# ip_phone_f_power.net
KiCad netlist of a schematic drawn in Altium Designer
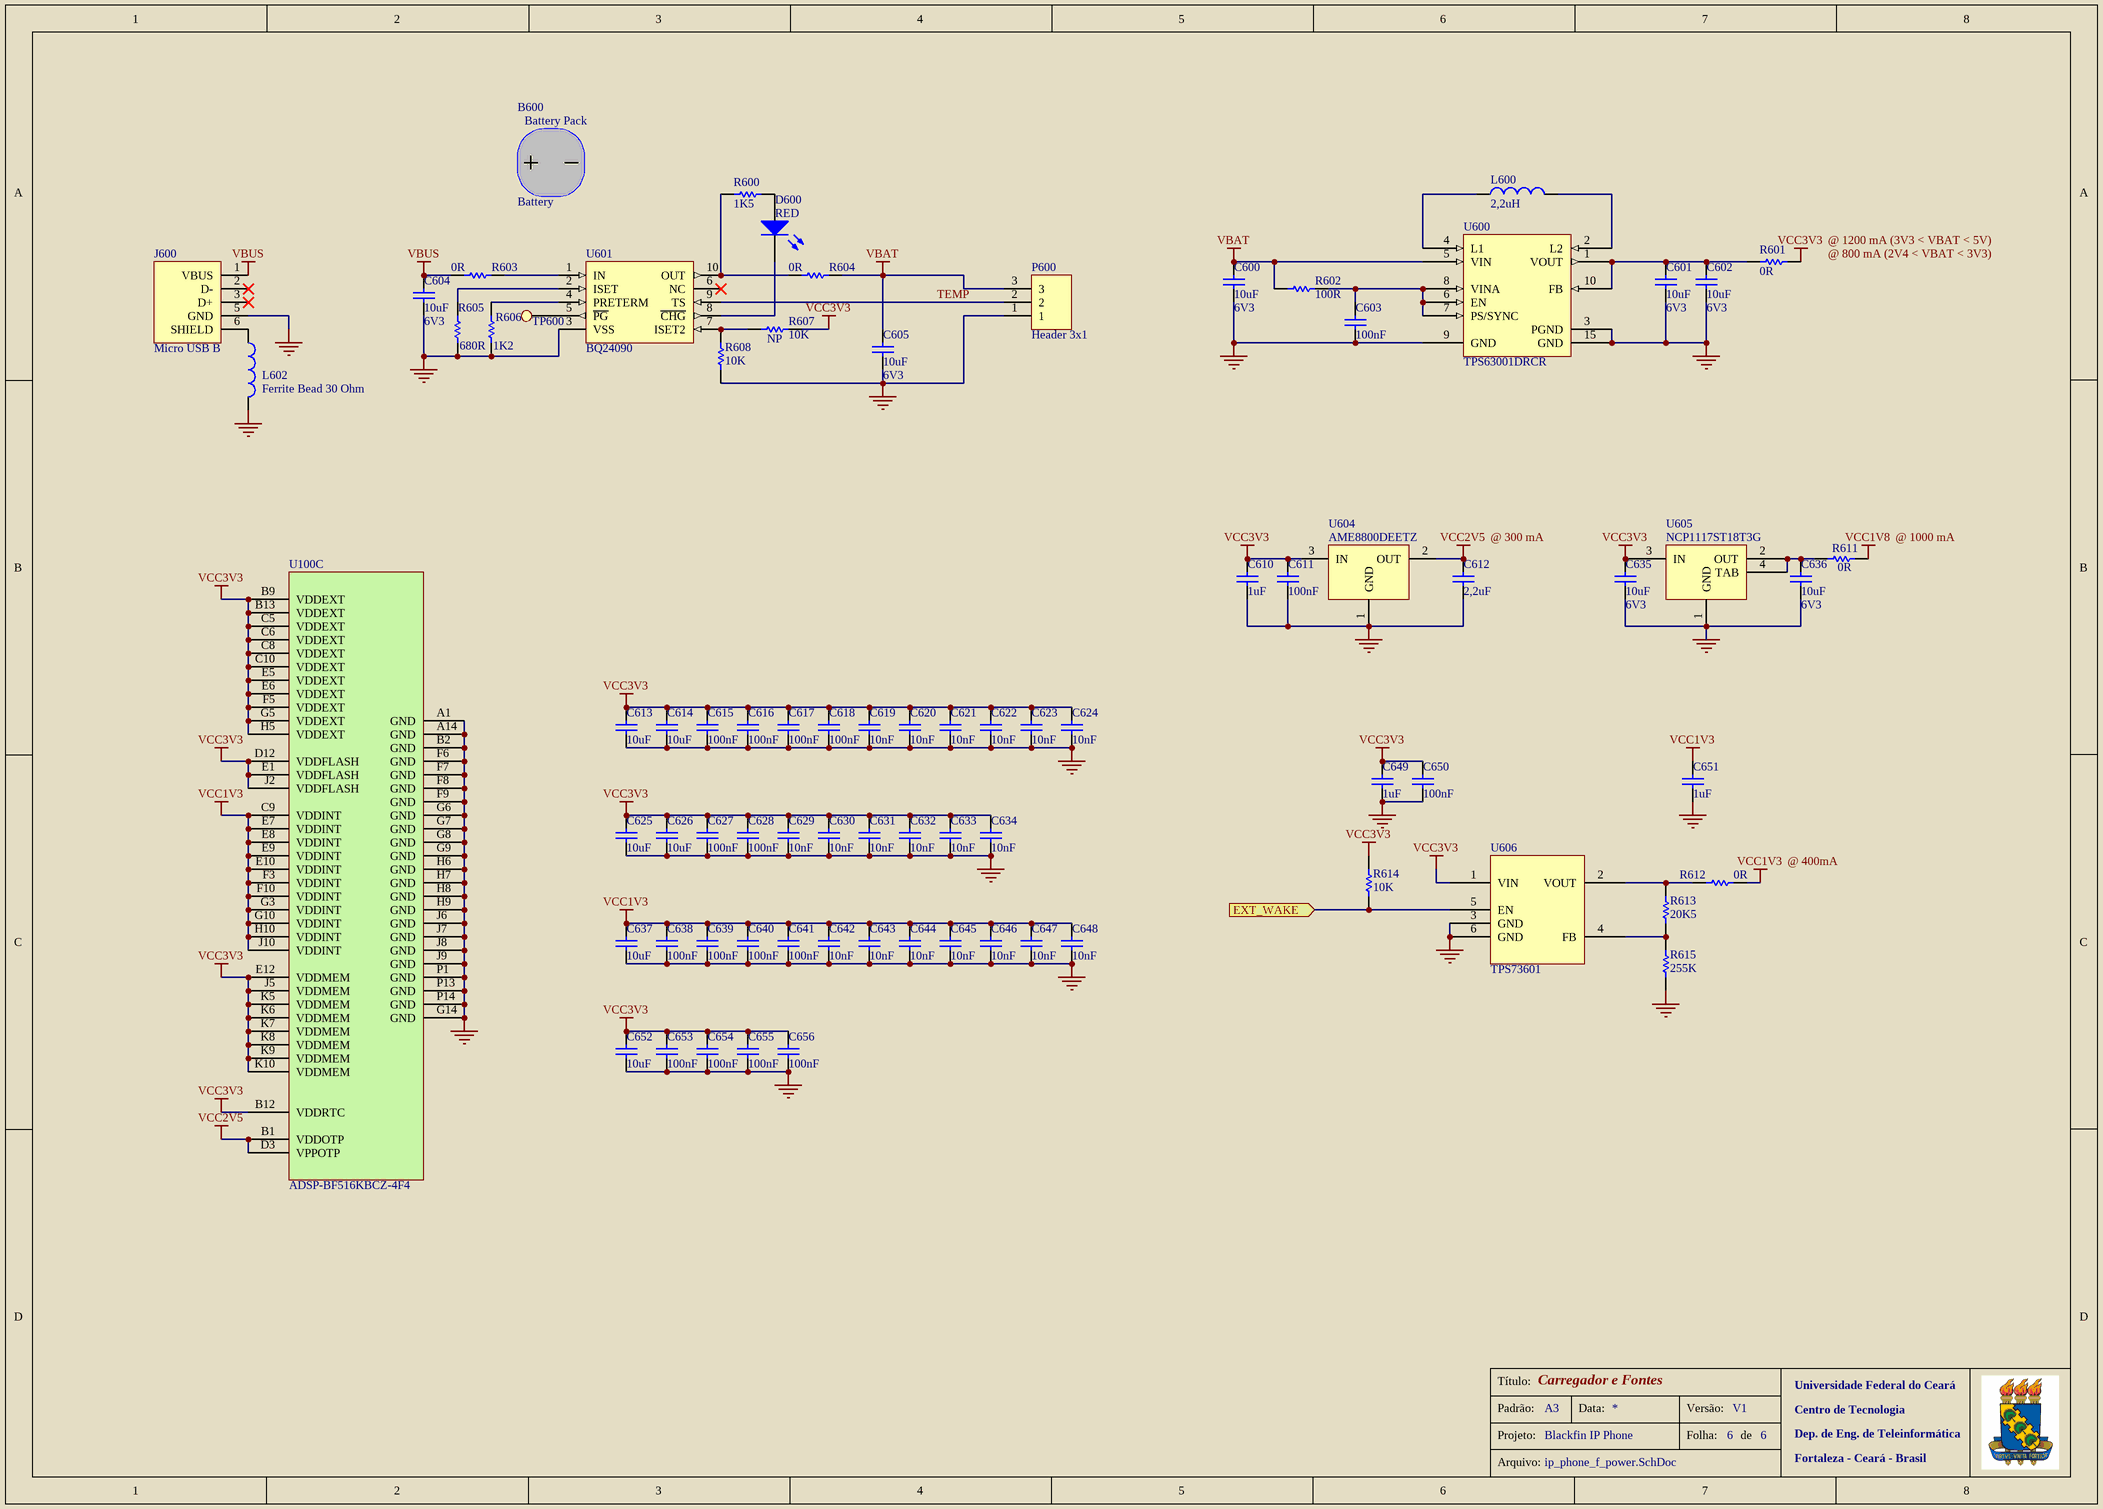
[diagram p0: ip_phone_f_power.SchDoc]

(export (version "E")
  (design (tool "Eeschema 10.0.6"))
  (components
    (comp (ref "B600")
      (value "Battery")
      (description "Li-Polymer battery PL714065, 3.7V 2000mAh cell")
      (fields (field (name "EVENDORPART#") "PC-714065") (field (name "MANUFACTURER") "HOLY TECHNOLOGY"))
      (libsource (lib "ip_phone") (part "Battery"))
    )
    (comp (ref "C600")
      (value "10uF")
      (footprint "ip_phone:CC1608-0603")
      (description "Capacitor SMD/SMT 0603 10uF 6.3volts X5R 20%")
      (fields (field (name "EVENDORPART#") "810-C2012Y5V1A106Z") (field (name "MANUFACTURER") "TDK"))
      (libsource (lib "ip_phone") (part "Capacitor"))
    )
    (comp (ref "C601")
      (value "10uF")
      (footprint "ip_phone:CC1608-0603")
      (description "Capacitor SMD/SMT 0603 10uF 6.3volts X5R 20%")
      (fields (field (name "EVENDORPART#") "810-C2012Y5V1A106Z") (field (name "MANUFACTURER") "TDK"))
      (libsource (lib "ip_phone") (part "Capacitor"))
    )
    (comp (ref "C602")
      (value "10uF")
      (footprint "ip_phone:CC1608-0603")
      (description "Capacitor SMD/SMT 0603 10uF 6.3volts X5R 20%")
      (fields (field (name "EVENDORPART#") "810-C2012Y5V1A106Z") (field (name "MANUFACTURER") "TDK"))
      (libsource (lib "ip_phone") (part "Capacitor"))
    )
    (comp (ref "C603")
      (value "100nF")
      (footprint "ip_phone:CC1005-0402")
      (description "MLCC - SMD/SMT 0.1UF 16V 10% 0402")
      (fields (field (name "EVENDORPART#") "810-C1005X7R1C104K") (field (name "MANUFACTURER") "TDK"))
      (libsource (lib "ip_phone") (part "Capacitor"))
    )
    (comp (ref "C604")
      (value "10uF")
      (footprint "ip_phone:CC1608-0603")
      (description "Capacitor SMD/SMT 0603 10uF 6.3volts X5R 20%")
      (fields (field (name "EVENDORPART#") "810-C2012Y5V1A106Z") (field (name "MANUFACTURER") "TDK"))
      (libsource (lib "ip_phone") (part "Capacitor"))
    )
    (comp (ref "C605")
      (value "10uF")
      (footprint "ip_phone:CC1608-0603")
      (description "Capacitor SMD/SMT 0603 10uF 6.3volts X5R 20%")
      (fields (field (name "EVENDORPART#") "810-C2012Y5V1A106Z") (field (name "MANUFACTURER") "TDK"))
      (libsource (lib "ip_phone") (part "Capacitor"))
    )
    (comp (ref "C610")
      (value "1uF")
      (footprint "ip_phone:CC1005-0402")
      (description "CAP CER 1.0UF 6.3V 20% X5R 0402")
      (fields
        (field (name "EVENDORPART#") "490-1319-1-ND")
        (field (name "MANUFACTURER") "Murata Electronics North America")
      )
      (libsource (lib "ip_phone") (part "Capacitor"))
    )
    (comp (ref "C611")
      (value "100nF")
      (footprint "ip_phone:CC1005-0402")
      (description "MLCC - SMD/SMT 0.1UF 16V 10% 0402")
      (fields (field (name "EVENDORPART#") "810-C1005X7R1C104K") (field (name "MANUFACTURER") "TDK"))
      (libsource (lib "ip_phone") (part "Capacitor"))
    )
    (comp (ref "C612")
      (value "2,2uF")
      (footprint "ip_phone:CC1608-0603")
      (description "Capacitor SMD/SMT 0603 2.2uF 10volts Y5V +80-20%")
      (fields (field (name "EVENDORPART#") "81-GRM188F51A225ZE01") (field (name "MANUFACTURER") "Murata"))
      (libsource (lib "ip_phone") (part "Capacitor"))
    )
    (comp (ref "C613")
      (value "10uF")
      (footprint "ip_phone:CC1608-0603")
      (description "Capacitor SMD/SMT 0603 10uF 6.3volts X5R 20%")
      (fields (field (name "EVENDORPART#") "810-C2012Y5V1A106Z") (field (name "MANUFACTURER") "TDK"))
      (libsource (lib "ip_phone") (part "Capacitor"))
    )
    (comp (ref "C614")
      (value "10uF")
      (footprint "ip_phone:CC1608-0603")
      (description "Capacitor SMD/SMT 0603 10uF 6.3volts X5R 20%")
      (fields (field (name "EVENDORPART#") "810-C2012Y5V1A106Z") (field (name "MANUFACTURER") "TDK"))
      (libsource (lib "ip_phone") (part "Capacitor"))
    )
    (comp (ref "C615")
      (value "100nF")
      (footprint "ip_phone:CC1005-0402")
      (description "MLCC - SMD/SMT 0.1UF 16V 10% 0402")
      (fields (field (name "EVENDORPART#") "810-C1005X7R1C104K") (field (name "MANUFACTURER") "TDK"))
      (libsource (lib "ip_phone") (part "Capacitor"))
    )
    (comp (ref "C616")
      (value "100nF")
      (footprint "ip_phone:CC1005-0402")
      (description "MLCC - SMD/SMT 0.1UF 16V 10% 0402")
      (fields (field (name "EVENDORPART#") "810-C1005X7R1C104K") (field (name "MANUFACTURER") "TDK"))
      (libsource (lib "ip_phone") (part "Capacitor"))
    )
    (comp (ref "C617")
      (value "100nF")
      (footprint "ip_phone:CC1005-0402")
      (description "MLCC - SMD/SMT 0.1UF 16V 10% 0402")
      (fields (field (name "EVENDORPART#") "810-C1005X7R1C104K") (field (name "MANUFACTURER") "TDK"))
      (libsource (lib "ip_phone") (part "Capacitor"))
    )
    (comp (ref "C618")
      (value "100nF")
      (footprint "ip_phone:CC1005-0402")
      (description "MLCC - SMD/SMT 0.1UF 16V 10% 0402")
      (fields (field (name "EVENDORPART#") "810-C1005X7R1C104K") (field (name "MANUFACTURER") "TDK"))
      (libsource (lib "ip_phone") (part "Capacitor"))
    )
    (comp (ref "C619")
      (value "10nF")
      (footprint "ip_phone:CC1005-0402")
      (description "Capacitor SMD/SMT 0402 0.01uF 16volts X7R 10%")
      (fields (field (name "EVENDORPART#") "810-C1005X7R1C103K") (field (name "MANUFACTURER") "TDK"))
      (libsource (lib "ip_phone") (part "Capacitor"))
    )
    (comp (ref "C620")
      (value "10nF")
      (footprint "ip_phone:CC1005-0402")
      (description "Capacitor SMD/SMT 0402 0.01uF 16volts X7R 10%")
      (fields (field (name "EVENDORPART#") "810-C1005X7R1C103K") (field (name "MANUFACTURER") "TDK"))
      (libsource (lib "ip_phone") (part "Capacitor"))
    )
    (comp (ref "C621")
      (value "10nF")
      (footprint "ip_phone:CC1005-0402")
      (description "Capacitor SMD/SMT 0402 0.01uF 16volts X7R 10%")
      (fields (field (name "EVENDORPART#") "810-C1005X7R1C103K") (field (name "MANUFACTURER") "TDK"))
      (libsource (lib "ip_phone") (part "Capacitor"))
    )
    (comp (ref "C622")
      (value "10nF")
      (footprint "ip_phone:CC1005-0402")
      (description "Capacitor SMD/SMT 0402 0.01uF 16volts X7R 10%")
      (fields (field (name "EVENDORPART#") "810-C1005X7R1C103K") (field (name "MANUFACTURER") "TDK"))
      (libsource (lib "ip_phone") (part "Capacitor"))
    )
    (comp (ref "C623")
      (value "10nF")
      (footprint "ip_phone:CC1005-0402")
      (description "Capacitor SMD/SMT 0402 0.01uF 16volts X7R 10%")
      (fields (field (name "EVENDORPART#") "810-C1005X7R1C103K") (field (name "MANUFACTURER") "TDK"))
      (libsource (lib "ip_phone") (part "Capacitor"))
    )
    (comp (ref "C624")
      (value "10nF")
      (footprint "ip_phone:CC1005-0402")
      (description "Capacitor SMD/SMT 0402 0.01uF 16volts X7R 10%")
      (fields (field (name "EVENDORPART#") "810-C1005X7R1C103K") (field (name "MANUFACTURER") "TDK"))
      (libsource (lib "ip_phone") (part "Capacitor"))
    )
    (comp (ref "C625")
      (value "10uF")
      (footprint "ip_phone:CC1608-0603")
      (description "Capacitor SMD/SMT 0603 10uF 6.3volts X5R 20%")
      (fields (field (name "EVENDORPART#") "810-C2012Y5V1A106Z") (field (name "MANUFACTURER") "TDK"))
      (libsource (lib "ip_phone") (part "Capacitor"))
    )
    (comp (ref "C626")
      (value "10uF")
      (footprint "ip_phone:CC1608-0603")
      (description "Capacitor SMD/SMT 0603 10uF 6.3volts X5R 20%")
      (fields (field (name "EVENDORPART#") "810-C2012Y5V1A106Z") (field (name "MANUFACTURER") "TDK"))
      (libsource (lib "ip_phone") (part "Capacitor"))
    )
    (comp (ref "C627")
      (value "100nF")
      (footprint "ip_phone:CC1005-0402")
      (description "MLCC - SMD/SMT 0.1UF 16V 10% 0402")
      (fields (field (name "EVENDORPART#") "810-C1005X7R1C104K") (field (name "MANUFACTURER") "TDK"))
      (libsource (lib "ip_phone") (part "Capacitor"))
    )
    (comp (ref "C628")
      (value "100nF")
      (footprint "ip_phone:CC1005-0402")
      (description "MLCC - SMD/SMT 0.1UF 16V 10% 0402")
      (fields (field (name "EVENDORPART#") "810-C1005X7R1C104K") (field (name "MANUFACTURER") "TDK"))
      (libsource (lib "ip_phone") (part "Capacitor"))
    )
    (comp (ref "C629")
      (value "10nF")
      (footprint "ip_phone:CC1005-0402")
      (description "Capacitor SMD/SMT 0402 0.01uF 16volts X7R 10%")
      (fields (field (name "EVENDORPART#") "810-C1005X7R1C103K") (field (name "MANUFACTURER") "TDK"))
      (libsource (lib "ip_phone") (part "Capacitor"))
    )
    (comp (ref "C630")
      (value "10nF")
      (footprint "ip_phone:CC1005-0402")
      (description "Capacitor SMD/SMT 0402 0.01uF 16volts X7R 10%")
      (fields (field (name "EVENDORPART#") "810-C1005X7R1C103K") (field (name "MANUFACTURER") "TDK"))
      (libsource (lib "ip_phone") (part "Capacitor"))
    )
    (comp (ref "C631")
      (value "10nF")
      (footprint "ip_phone:CC1005-0402")
      (description "Capacitor SMD/SMT 0402 0.01uF 16volts X7R 10%")
      (fields (field (name "EVENDORPART#") "810-C1005X7R1C103K") (field (name "MANUFACTURER") "TDK"))
      (libsource (lib "ip_phone") (part "Capacitor"))
    )
    (comp (ref "C632")
      (value "10nF")
      (footprint "ip_phone:CC1005-0402")
      (description "Capacitor SMD/SMT 0402 0.01uF 16volts X7R 10%")
      (fields (field (name "EVENDORPART#") "810-C1005X7R1C103K") (field (name "MANUFACTURER") "TDK"))
      (libsource (lib "ip_phone") (part "Capacitor"))
    )
    (comp (ref "C633")
      (value "10nF")
      (footprint "ip_phone:CC1005-0402")
      (description "Capacitor SMD/SMT 0402 0.01uF 16volts X7R 10%")
      (fields (field (name "EVENDORPART#") "810-C1005X7R1C103K") (field (name "MANUFACTURER") "TDK"))
      (libsource (lib "ip_phone") (part "Capacitor"))
    )
    (comp (ref "C634")
      (value "10nF")
      (footprint "ip_phone:CC1005-0402")
      (description "Capacitor SMD/SMT 0402 0.01uF 16volts X7R 10%")
      (fields (field (name "EVENDORPART#") "810-C1005X7R1C103K") (field (name "MANUFACTURER") "TDK"))
      (libsource (lib "ip_phone") (part "Capacitor"))
    )
    (comp (ref "C635")
      (value "10uF")
      (footprint "ip_phone:CC1608-0603")
      (description "Capacitor SMD/SMT 0603 10uF 6.3volts X5R 20%")
      (fields (field (name "EVENDORPART#") "810-C2012Y5V1A106Z") (field (name "MANUFACTURER") "TDK"))
      (libsource (lib "ip_phone") (part "Capacitor"))
    )
    (comp (ref "C636")
      (value "10uF")
      (footprint "ip_phone:CC1608-0603")
      (description "Capacitor SMD/SMT 0603 10uF 6.3volts X5R 20%")
      (fields (field (name "EVENDORPART#") "810-C2012Y5V1A106Z") (field (name "MANUFACTURER") "TDK"))
      (libsource (lib "ip_phone") (part "Capacitor"))
    )
    (comp (ref "C637")
      (value "10uF")
      (footprint "ip_phone:CC1608-0603")
      (description "Capacitor SMD/SMT 0603 10uF 6.3volts X5R 20%")
      (fields (field (name "EVENDORPART#") "810-C2012Y5V1A106Z") (field (name "MANUFACTURER") "TDK"))
      (libsource (lib "ip_phone") (part "Capacitor"))
    )
    (comp (ref "C638")
      (value "100nF")
      (footprint "ip_phone:CC1005-0402")
      (description "MLCC - SMD/SMT 0.1UF 16V 10% 0402")
      (fields (field (name "EVENDORPART#") "810-C1005X7R1C104K") (field (name "MANUFACTURER") "TDK"))
      (libsource (lib "ip_phone") (part "Capacitor"))
    )
    (comp (ref "C639")
      (value "100nF")
      (footprint "ip_phone:CC1005-0402")
      (description "MLCC - SMD/SMT 0.1UF 16V 10% 0402")
      (fields (field (name "EVENDORPART#") "810-C1005X7R1C104K") (field (name "MANUFACTURER") "TDK"))
      (libsource (lib "ip_phone") (part "Capacitor"))
    )
    (comp (ref "C640")
      (value "100nF")
      (footprint "ip_phone:CC1005-0402")
      (description "MLCC - SMD/SMT 0.1UF 16V 10% 0402")
      (fields (field (name "EVENDORPART#") "810-C1005X7R1C104K") (field (name "MANUFACTURER") "TDK"))
      (libsource (lib "ip_phone") (part "Capacitor"))
    )
    (comp (ref "C641")
      (value "100nF")
      (footprint "ip_phone:CC1005-0402")
      (description "MLCC - SMD/SMT 0.1UF 16V 10% 0402")
      (fields (field (name "EVENDORPART#") "810-C1005X7R1C104K") (field (name "MANUFACTURER") "TDK"))
      (libsource (lib "ip_phone") (part "Capacitor"))
    )
    (comp (ref "C642")
      (value "10nF")
      (footprint "ip_phone:CC1005-0402")
      (description "Capacitor SMD/SMT 0402 0.01uF 16volts X7R 10%")
      (fields (field (name "EVENDORPART#") "810-C1005X7R1C103K") (field (name "MANUFACTURER") "TDK"))
      (libsource (lib "ip_phone") (part "Capacitor"))
    )
    (comp (ref "C643")
      (value "10nF")
      (footprint "ip_phone:CC1005-0402")
      (description "Capacitor SMD/SMT 0402 0.01uF 16volts X7R 10%")
      (fields (field (name "EVENDORPART#") "810-C1005X7R1C103K") (field (name "MANUFACTURER") "TDK"))
      (libsource (lib "ip_phone") (part "Capacitor"))
    )
    (comp (ref "C644")
      (value "10nF")
      (footprint "ip_phone:CC1005-0402")
      (description "Capacitor SMD/SMT 0402 0.01uF 16volts X7R 10%")
      (fields (field (name "EVENDORPART#") "810-C1005X7R1C103K") (field (name "MANUFACTURER") "TDK"))
      (libsource (lib "ip_phone") (part "Capacitor"))
    )
    (comp (ref "C645")
      (value "10nF")
      (footprint "ip_phone:CC1005-0402")
      (description "Capacitor SMD/SMT 0402 0.01uF 16volts X7R 10%")
      (fields (field (name "EVENDORPART#") "810-C1005X7R1C103K") (field (name "MANUFACTURER") "TDK"))
      (libsource (lib "ip_phone") (part "Capacitor"))
    )
    (comp (ref "C646")
      (value "10nF")
      (footprint "ip_phone:CC1005-0402")
      (description "Capacitor SMD/SMT 0402 0.01uF 16volts X7R 10%")
      (fields (field (name "EVENDORPART#") "810-C1005X7R1C103K") (field (name "MANUFACTURER") "TDK"))
      (libsource (lib "ip_phone") (part "Capacitor"))
    )
    (comp (ref "C647")
      (value "10nF")
      (footprint "ip_phone:CC1005-0402")
      (description "Capacitor SMD/SMT 0402 0.01uF 16volts X7R 10%")
      (fields (field (name "EVENDORPART#") "810-C1005X7R1C103K") (field (name "MANUFACTURER") "TDK"))
      (libsource (lib "ip_phone") (part "Capacitor"))
    )
    (comp (ref "C648")
      (value "10nF")
      (footprint "ip_phone:CC1005-0402")
      (description "Capacitor SMD/SMT 0402 0.01uF 16volts X7R 10%")
      (fields (field (name "EVENDORPART#") "810-C1005X7R1C103K") (field (name "MANUFACTURER") "TDK"))
      (libsource (lib "ip_phone") (part "Capacitor"))
    )
    (comp (ref "C649")
      (value "1uF")
      (footprint "ip_phone:CC1005-0402")
      (description "CAP CER 1.0UF 6.3V 20% X5R 0402")
      (fields
        (field (name "EVENDORPART#") "490-1319-1-ND")
        (field (name "MANUFACTURER") "Murata Electronics North America")
      )
      (libsource (lib "ip_phone") (part "Capacitor"))
    )
    (comp (ref "C650")
      (value "100nF")
      (footprint "ip_phone:CC1005-0402")
      (description "MLCC - SMD/SMT 0.1UF 16V 10% 0402")
      (fields (field (name "EVENDORPART#") "810-C1005X7R1C104K") (field (name "MANUFACTURER") "TDK"))
      (libsource (lib "ip_phone") (part "Capacitor"))
    )
    (comp (ref "C651")
      (value "1uF")
      (footprint "ip_phone:CC1005-0402")
      (description "CAP CER 1.0UF 6.3V 20% X5R 0402")
      (fields
        (field (name "EVENDORPART#") "490-1319-1-ND")
        (field (name "MANUFACTURER") "Murata Electronics North America")
      )
      (libsource (lib "ip_phone") (part "Capacitor"))
    )
    (comp (ref "C652")
      (value "10uF")
      (footprint "ip_phone:CC1608-0603")
      (description "Capacitor SMD/SMT 0603 10uF 6.3volts X5R 20%")
      (fields (field (name "EVENDORPART#") "810-C2012Y5V1A106Z") (field (name "MANUFACTURER") "TDK"))
      (libsource (lib "ip_phone") (part "Capacitor"))
    )
    (comp (ref "C653")
      (value "100nF")
      (footprint "ip_phone:CC1005-0402")
      (description "MLCC - SMD/SMT 0.1UF 16V 10% 0402")
      (fields (field (name "EVENDORPART#") "810-C1005X7R1C104K") (field (name "MANUFACTURER") "TDK"))
      (libsource (lib "ip_phone") (part "Capacitor"))
    )
    (comp (ref "C654")
      (value "100nF")
      (footprint "ip_phone:CC1005-0402")
      (description "MLCC - SMD/SMT 0.1UF 16V 10% 0402")
      (fields (field (name "EVENDORPART#") "810-C1005X7R1C104K") (field (name "MANUFACTURER") "TDK"))
      (libsource (lib "ip_phone") (part "Capacitor"))
    )
    (comp (ref "C655")
      (value "100nF")
      (footprint "ip_phone:CC1005-0402")
      (description "MLCC - SMD/SMT 0.1UF 16V 10% 0402")
      (fields (field (name "EVENDORPART#") "810-C1005X7R1C104K") (field (name "MANUFACTURER") "TDK"))
      (libsource (lib "ip_phone") (part "Capacitor"))
    )
    (comp (ref "C656")
      (value "100nF")
      (footprint "ip_phone:CC1005-0402")
      (description "MLCC - SMD/SMT 0.1UF 16V 10% 0402")
      (fields (field (name "EVENDORPART#") "810-C1005X7R1C104K") (field (name "MANUFACTURER") "TDK"))
      (libsource (lib "ip_phone") (part "Capacitor"))
    )
    (comp (ref "D600")
      (value "RED")
      (footprint "ip_phone:LED_0603")
      (description "LED")
      (fields (field (name "PART#") "APT1608SURCK") (field (name "MANUFACTURER") "Kingbright"))
      (libsource (lib "ip_phone") (part "LED"))
    )
    (comp (ref "J600")
      (value "Micro USB B")
      (footprint "ip_phone:Micro USB")
      (description "USB Connectors 5P Quick Connect Micro USB TypeB Rcpt")
      (fields (field (name "MANUFACTURER") "FCI") (field (name "PART#") "10103594-0001LF"))
      (libsource (lib "ip_phone") (part "CON_Micro_USB"))
    )
    (comp (ref "L600")
      (value "2,2uH")
      (footprint "ip_phone:POWER INDUCTOR")
      (description "IND POWER 2.2UH 1.5A SMD")
      (fields (field (name "EVENDORPART#") "445-3233-1-ND") (field (name "MANUFACTURER") "TDK"))
      (libsource (lib "ip_phone") (part "Inductor"))
    )
    (comp (ref "L602")
      (value "Ferrite Bead 30 Ohm")
      (footprint "ip_phone:INDUTOR_0603")
      (description "EMI/RFI Suppressors & Ferrites 0603 30 OHM")
      (fields (field (name "EVENDORPART#") "81-BLM11P300S") (field (name "MANUFACTURER") "Murata"))
      (libsource (lib "ip_phone") (part "Inductor"))
    )
    (comp (ref "P600")
      (value "Header 3x1")
      (footprint "ip_phone:HEADER 3x1")
      (description "CONN HEADER 3POS 2.5MM R/A SMD")
      (fields
        (field (name "MANUFACTURER") "JST Sales America Inc")
        (field (name "PART#") "S3B-XH-SM4-TB(LF)(SN)")
      )
      (libsource (lib "ip_phone") (part "CON_HEADER_3x1"))
    )
    (comp (ref "R600")
      (value "1K5")
      (footprint "ip_phone:CR1608-0603")
      (description "Thick Film Resistors 1.5KOHM 5% 1/10W")
      (fields (field (name "EVENDORPART#") "52-CR0603-JW-152GLF") (field (name "MANUFACTURER") "Bourns"))
      (libsource (lib "ip_phone") (part "Resistor"))
    )
    (comp (ref "R601")
      (value "0R")
      (footprint "ip_phone:CR3225-1210")
      (description "Thick Film Resistors ZERO OHM JUMPER 1210")
      (fields (field (name "EVENDORPART#") "660-RK73Z2ETTD") (field (name "MANUFACTURER") "KOA Speer"))
      (libsource (lib "ip_phone") (part "Resistor"))
    )
    (comp (ref "R602")
      (value "100R")
      (footprint "ip_phone:CR1608-0603")
      (description "Thick Film Resistors 1/16WATT 100R 0402")
      (fields (field (name "EVENDORPART#") "652-CR0603-JW-101GLF") (field (name "MANUFACTURER") "Bourns"))
      (libsource (lib "ip_phone") (part "Resistor"))
    )
    (comp (ref "R603")
      (value "0R")
      (footprint "ip_phone:CR1608-0603")
      (description "Thick Film Resistors ZERO OHM")
      (fields (field (name "EVENDORPART#") "652-CR0603-J/-000ELF") (field (name "MANUFACTURER") "Bourns"))
      (libsource (lib "ip_phone") (part "Resistor"))
    )
    (comp (ref "R604")
      (value "0R")
      (footprint "ip_phone:CR1608-0603")
      (description "Thick Film Resistors ZERO OHM")
      (fields (field (name "EVENDORPART#") "652-CR0603-J/-000ELF") (field (name "MANUFACTURER") "Bourns"))
      (libsource (lib "ip_phone") (part "Resistor"))
    )
    (comp (ref "R605")
      (value "680R")
      (footprint "ip_phone:CR1005-0402")
      (description "Thick Film Resistors SMD 0402 680 5%  1/16 W")
      (fields (field (name "EVENDORPART#") "311-680JRCT-ND") (field (name "MANUFACTURER") "Yageo"))
      (libsource (lib "ip_phone") (part "Resistor"))
    )
    (comp (ref "R606")
      (value "1K2")
      (footprint "ip_phone:CR1005-0402")
      (description "Thick Film Resistors SMD 0402 1K2 5%  1/16 W")
      (fields (field (name "EVENDORPART#") "311-1.2KJRCT-ND") (field (name "MANUFACTURER") "Yageo"))
      (libsource (lib "ip_phone") (part "Resistor"))
    )
    (comp (ref "R607")
      (value "10K")
      (footprint "ip_phone:CR1005-0402")
      (description "Thick Film Resistors SMD 0402 10k 5%  1/16 W")
      (fields
        (field (name "EVENDORPART#") "311-10KJRCT-ND")
        (field (name "MANUFACTURER") "Yageo")
        (field (name "NP") "NP")
      )
      (libsource (lib "ip_phone") (part "Resistor"))
    )
    (comp (ref "R608")
      (value "10K")
      (footprint "ip_phone:CR1005-0402")
      (description "Thick Film Resistors SMD 0402 10k 5%  1/16 W")
      (fields (field (name "EVENDORPART#") "311-10KJRCT-ND") (field (name "MANUFACTURER") "Yageo"))
      (libsource (lib "ip_phone") (part "Resistor"))
    )
    (comp (ref "R611")
      (value "0R")
      (footprint "ip_phone:CR3225-1210")
      (description "Thick Film Resistors ZERO OHM JUMPER 1210")
      (fields (field (name "EVENDORPART#") "660-RK73Z2ETTD") (field (name "MANUFACTURER") "KOA Speer"))
      (libsource (lib "ip_phone") (part "Resistor"))
    )
    (comp (ref "R612")
      (value "0R")
      (footprint "ip_phone:CR1608-0603")
      (description "Thick Film Resistors ZERO OHM")
      (fields (field (name "EVENDORPART#") "652-CR0603-J/-000ELF") (field (name "MANUFACTURER") "Bourns"))
      (libsource (lib "ip_phone") (part "Resistor"))
    )
    (comp (ref "R613")
      (value "20K5")
      (footprint "ip_phone:CR1005-0402")
      (description "RES 20.5K OHM 1/10W 1% 0402 SMD")
      (fields (field (name "EVENDORPART#") "P20.5KLCT-ND") (field (name "MANUFACTURER") "Panasonic - ECG"))
      (libsource (lib "ip_phone") (part "Resistor"))
    )
    (comp (ref "R614")
      (value "10K")
      (footprint "ip_phone:CR1005-0402")
      (description "Thick Film Resistors SMD 0402 10k 5%  1/16 W")
      (fields (field (name "EVENDORPART#") "311-10KJRCT-ND") (field (name "MANUFACTURER") "Yageo"))
      (libsource (lib "ip_phone") (part "Resistor"))
    )
    (comp (ref "R615")
      (value "255K")
      (footprint "ip_phone:CR1005-0402")
      (description "RES 255K OHM 1/10W 1% 0402 SMD")
      (fields (field (name "EVENDORPART#") "P255KLCT-ND") (field (name "MANUFACTURER") "Panasonic - ECG"))
      (libsource (lib "ip_phone") (part "Resistor"))
    )
    (comp (ref "TP600")
      (value "Test Point")
      (footprint "ip_phone:Test Point")
      (fields (field (name "EVENDORPART#") "NÃO SE APLICA"))
      (libsource (lib "ip_phone") (part "Test Point"))
    )
    (comp (ref "U100")
      (value "ADSP-BF516KBCZ-4F4")
      (footprint "ip_phone:BGA168")
      (description "Low Power Blackfin with Advanced Embedded Connectivity")
      (fields (field (name "MANUFACTURER") "Analog Device"))
      (libsource (lib "ip_phone") (part "ADSP-BF516KBCZ-4F4"))
    )
    (comp (ref "U600")
      (value "TPS63001DRCR")
      (footprint "ip_phone:SON10")
      (description "HIGH EFFICIENT SINGLE INDUCTOR BUCK-BOOST CONVERTER WITH 1.8-A SWITCHES")
      (fields
        (field (name "EVENDORPART#") "296-19643-1-ND")
        (field (name "MANUFACTURER") "Texas Instruments")
      )
      (libsource (lib "ip_phone") (part "TPS63001DRCR"))
    )
    (comp (ref "U601")
      (value "BQ24090")
      (footprint "ip_phone:MSOP10")
      (description "1A,Sgl Inp,Sgl Cell Li-Ion Batt Charger")
      (fields (field (name "MANUFACTURER") "Texas Instruments") (field (name "PART#") "BQ24090DGQT"))
      (libsource (lib "ip_phone") (part "BQ24090"))
    )
    (comp (ref "U604")
      (value "AME8800DEETZ")
      (footprint "ip_phone:SOT-23")
      (description "Low Dropout (LDO) Regulators 2.5V 300mA CMOS")
      (fields (field (name "EVENDORPART#") "827-AME8800DEETZ") (field (name "MANUFACTURER") "AME"))
      (libsource (lib "ip_phone") (part "AME8800DEETZ"))
    )
    (comp (ref "U605")
      (value "NCP1117ST18T3G")
      (footprint "ip_phone:SOT223")
      (description "Low Dropout (LDO) Regulators 1.8V 1A Positive")
      (fields
        (field (name "EVENDORPART#") "863-NCP1117ST18T3G")
        (field (name "MANUFACTURER") "ON Semiconductor")
      )
      (libsource (lib "ip_phone") (part "NCP1117ST18T3G"))
    )
    (comp (ref "U606")
      (value "TPS73601")
      (footprint "ip_phone:SOT223 - 6P")
      (description "LDO Regulator")
      (fields (field (name "PART#") "TPS73601DCQR") (field (name "EVENDORPART#") "595-TPS73601DCQR"))
      (libsource (lib "ip_phone") (part "TPS73601"))
    )
  )
  (nets
    (net (code "1") (name "/EXT_WAKE") (class "Default")
      (node (ref "R614") (pin "2") (pinfunction "2_2") (pintype "passive"))
      (node (ref "U606") (pin "5") (pinfunction "EN_5") (pintype "passive"))
    )
    (net (code "2") (name "/TEMP") (class "Default")
      (node (ref "P600") (pin "2") (pinfunction "2_2") (pintype "passive"))
      (node (ref "U601") (pin "9") (pinfunction "TS_9") (pintype "input"))
    )
    (net (code "3") (name "GND") (class "Default")
      (node (ref "C600") (pin "1") (pinfunction "1_1") (pintype "passive"))
      (node (ref "C601") (pin "1") (pinfunction "1_1") (pintype "passive"))
      (node (ref "C602") (pin "1") (pinfunction "1_1") (pintype "passive"))
      (node (ref "C603") (pin "1") (pinfunction "1_1") (pintype "passive"))
      (node (ref "C604") (pin "1") (pinfunction "1_1") (pintype "passive"))
      (node (ref "C605") (pin "1") (pinfunction "1_1") (pintype "passive"))
      (node (ref "C610") (pin "2") (pinfunction "2_2") (pintype "passive"))
      (node (ref "C611") (pin "1") (pinfunction "1_1") (pintype "passive"))
      (node (ref "C612") (pin "1") (pinfunction "1_1") (pintype "passive"))
      (node (ref "C613") (pin "1") (pinfunction "1_1") (pintype "passive"))
      (node (ref "C614") (pin "1") (pinfunction "1_1") (pintype "passive"))
      (node (ref "C615") (pin "1") (pinfunction "1_1") (pintype "passive"))
      (node (ref "C616") (pin "1") (pinfunction "1_1") (pintype "passive"))
      (node (ref "C617") (pin "1") (pinfunction "1_1") (pintype "passive"))
      (node (ref "C618") (pin "1") (pinfunction "1_1") (pintype "passive"))
      (node (ref "C619") (pin "1") (pinfunction "1_1") (pintype "passive"))
      (node (ref "C620") (pin "1") (pinfunction "1_1") (pintype "passive"))
      (node (ref "C621") (pin "1") (pinfunction "1_1") (pintype "passive"))
      (node (ref "C622") (pin "1") (pinfunction "1_1") (pintype "passive"))
      (node (ref "C623") (pin "1") (pinfunction "1_1") (pintype "passive"))
      (node (ref "C624") (pin "1") (pinfunction "1_1") (pintype "passive"))
      (node (ref "C625") (pin "1") (pinfunction "1_1") (pintype "passive"))
      (node (ref "C626") (pin "1") (pinfunction "1_1") (pintype "passive"))
      (node (ref "C627") (pin "1") (pinfunction "1_1") (pintype "passive"))
      (node (ref "C628") (pin "1") (pinfunction "1_1") (pintype "passive"))
      (node (ref "C629") (pin "1") (pinfunction "1_1") (pintype "passive"))
      (node (ref "C630") (pin "1") (pinfunction "1_1") (pintype "passive"))
      (node (ref "C631") (pin "1") (pinfunction "1_1") (pintype "passive"))
      (node (ref "C632") (pin "1") (pinfunction "1_1") (pintype "passive"))
      (node (ref "C633") (pin "1") (pinfunction "1_1") (pintype "passive"))
      (node (ref "C634") (pin "1") (pinfunction "1_1") (pintype "passive"))
      (node (ref "C635") (pin "1") (pinfunction "1_1") (pintype "passive"))
      (node (ref "C636") (pin "1") (pinfunction "1_1") (pintype "passive"))
      (node (ref "C637") (pin "1") (pinfunction "1_1") (pintype "passive"))
      (node (ref "C638") (pin "1") (pinfunction "1_1") (pintype "passive"))
      (node (ref "C639") (pin "1") (pinfunction "1_1") (pintype "passive"))
      (node (ref "C640") (pin "1") (pinfunction "1_1") (pintype "passive"))
      (node (ref "C641") (pin "1") (pinfunction "1_1") (pintype "passive"))
      (node (ref "C642") (pin "1") (pinfunction "1_1") (pintype "passive"))
      (node (ref "C643") (pin "1") (pinfunction "1_1") (pintype "passive"))
      (node (ref "C644") (pin "1") (pinfunction "1_1") (pintype "passive"))
      (node (ref "C645") (pin "1") (pinfunction "1_1") (pintype "passive"))
      (node (ref "C646") (pin "1") (pinfunction "1_1") (pintype "passive"))
      (node (ref "C647") (pin "1") (pinfunction "1_1") (pintype "passive"))
      (node (ref "C648") (pin "1") (pinfunction "1_1") (pintype "passive"))
      (node (ref "C649") (pin "2") (pinfunction "2_2") (pintype "passive"))
      (node (ref "C650") (pin "1") (pinfunction "1_1") (pintype "passive"))
      (node (ref "C651") (pin "2") (pinfunction "2_2") (pintype "passive"))
      (node (ref "C652") (pin "1") (pinfunction "1_1") (pintype "passive"))
      (node (ref "C653") (pin "1") (pinfunction "1_1") (pintype "passive"))
      (node (ref "C654") (pin "1") (pinfunction "1_1") (pintype "passive"))
      (node (ref "C655") (pin "1") (pinfunction "1_1") (pintype "passive"))
      (node (ref "C656") (pin "1") (pinfunction "1_1") (pintype "passive"))
      (node (ref "J600") (pin "5") (pinfunction "GND_5") (pintype "passive"))
      (node (ref "L602") (pin "2") (pinfunction "2_2") (pintype "passive"))
      (node (ref "P600") (pin "1") (pinfunction "1_1") (pintype "passive"))
      (node (ref "R605") (pin "1") (pinfunction "1_1") (pintype "passive"))
      (node (ref "R606") (pin "2") (pinfunction "2_2") (pintype "passive"))
      (node (ref "R608") (pin "2") (pinfunction "2_2") (pintype "passive"))
      (node (ref "R615") (pin "1") (pinfunction "1_1") (pintype "passive"))
      (node (ref "U100") (pin "A1") (pinfunction "GND_A1") (pintype "power_in"))
      (node (ref "U100") (pin "A14") (pinfunction "GND_A14") (pintype "power_in"))
      (node (ref "U100") (pin "B2") (pinfunction "GND_B2") (pintype "power_in"))
      (node (ref "U100") (pin "F6") (pinfunction "GND_F6") (pintype "power_in"))
      (node (ref "U100") (pin "F7") (pinfunction "GND_F7") (pintype "power_in"))
      (node (ref "U100") (pin "F8") (pinfunction "GND_F8") (pintype "power_in"))
      (node (ref "U100") (pin "F9") (pinfunction "GND_F9") (pintype "power_in"))
      (node (ref "U100") (pin "G14") (pinfunction "GND_G14") (pintype "power_in"))
      (node (ref "U100") (pin "G6") (pinfunction "GND_G6") (pintype "power_in"))
      (node (ref "U100") (pin "G7") (pinfunction "GND_G7") (pintype "power_in"))
      (node (ref "U100") (pin "G8") (pinfunction "GND_G8") (pintype "power_in"))
      (node (ref "U100") (pin "G9") (pinfunction "GND_G9") (pintype "power_in"))
      (node (ref "U100") (pin "H6") (pinfunction "GND_H6") (pintype "power_in"))
      (node (ref "U100") (pin "H7") (pinfunction "GND_H7") (pintype "power_in"))
      (node (ref "U100") (pin "H8") (pinfunction "GND_H8") (pintype "power_in"))
      (node (ref "U100") (pin "H9") (pinfunction "GND_H9") (pintype "power_in"))
      (node (ref "U100") (pin "J6") (pinfunction "GND_J6") (pintype "power_in"))
      (node (ref "U100") (pin "J7") (pinfunction "GND_J7") (pintype "power_in"))
      (node (ref "U100") (pin "J8") (pinfunction "GND_J8") (pintype "power_in"))
      (node (ref "U100") (pin "J9") (pinfunction "GND_J9") (pintype "power_in"))
      (node (ref "U100") (pin "P1") (pinfunction "GND_P1") (pintype "power_in"))
      (node (ref "U100") (pin "P13") (pinfunction "GND_P13") (pintype "power_in"))
      (node (ref "U100") (pin "P14") (pinfunction "GND_P14") (pintype "power_in"))
      (node (ref "U600") (pin "15") (pinfunction "GND_15") (pintype "power_in"))
      (node (ref "U600") (pin "3") (pinfunction "PGND_3") (pintype "power_in"))
      (node (ref "U600") (pin "9") (pinfunction "GND_9") (pintype "power_in"))
      (node (ref "U601") (pin "3") (pinfunction "VSS_3") (pintype "power_in"))
      (node (ref "U604") (pin "1") (pinfunction "GND_1") (pintype "passive"))
      (node (ref "U605") (pin "1") (pinfunction "GND_1") (pintype "power_in"))
      (node (ref "U606") (pin "3") (pinfunction "GND_3") (pintype "passive"))
      (node (ref "U606") (pin "6") (pinfunction "GND_6") (pintype "passive"))
    )
    (net (code "4") (name "Net-(D600-A)") (class "Default")
      (node (ref "D600") (pin "1") (pinfunction "A_1") (pintype "passive"))
      (node (ref "R600") (pin "1") (pinfunction "1_1") (pintype "passive"))
    )
    (net (code "5") (name "Net-(D600-K)") (class "Default")
      (node (ref "D600") (pin "2") (pinfunction "K_2") (pintype "passive"))
      (node (ref "U601") (pin "8") (pinfunction "~{CHG}_8") (pintype "output"))
    )
    (net (code "6") (name "Net-(J600-SHIELD)") (class "Default")
      (node (ref "J600") (pin "6") (pinfunction "SHIELD_6") (pintype "passive"))
      (node (ref "L602") (pin "1") (pinfunction "1_1") (pintype "passive"))
    )
    (net (code "7") (name "Net-(U600-EN)") (class "Default")
      (node (ref "C603") (pin "2") (pinfunction "2_2") (pintype "passive"))
      (node (ref "R602") (pin "1") (pinfunction "1_1") (pintype "passive"))
      (node (ref "U600") (pin "6") (pinfunction "EN_6") (pintype "input"))
      (node (ref "U600") (pin "7") (pinfunction "PS/SYNC_7") (pintype "input"))
      (node (ref "U600") (pin "8") (pinfunction "VINA_8") (pintype "input"))
    )
    (net (code "8") (name "Net-(U600-FB)") (class "Default")
      (node (ref "C601") (pin "2") (pinfunction "2_2") (pintype "passive"))
      (node (ref "C602") (pin "2") (pinfunction "2_2") (pintype "passive"))
      (node (ref "R601") (pin "1") (pinfunction "1_1") (pintype "passive"))
      (node (ref "U600") (pin "1") (pinfunction "VOUT_1") (pintype "output"))
      (node (ref "U600") (pin "10") (pinfunction "FB_10") (pintype "input"))
    )
    (net (code "9") (name "Net-(U600-L1)") (class "Default")
      (node (ref "L600") (pin "1") (pinfunction "1_1") (pintype "passive"))
      (node (ref "U600") (pin "4") (pinfunction "L1_4") (pintype "input"))
    )
    (net (code "10") (name "Net-(U600-L2)") (class "Default")
      (node (ref "L600") (pin "2") (pinfunction "2_2") (pintype "passive"))
      (node (ref "U600") (pin "2") (pinfunction "L2_2") (pintype "input"))
    )
    (net (code "11") (name "Net-(U601-IN)") (class "Default")
      (node (ref "R603") (pin "1") (pinfunction "1_1") (pintype "passive"))
      (node (ref "U601") (pin "1") (pinfunction "IN_1") (pintype "input"))
    )
    (net (code "12") (name "Net-(U601-ISET)") (class "Default")
      (node (ref "R605") (pin "2") (pinfunction "2_2") (pintype "passive"))
      (node (ref "U601") (pin "2") (pinfunction "ISET_2") (pintype "input"))
    )
    (net (code "13") (name "Net-(U601-ISET2)") (class "Default")
      (node (ref "R607") (pin "2") (pinfunction "2_2") (pintype "passive"))
      (node (ref "R608") (pin "1") (pinfunction "1_1") (pintype "passive"))
      (node (ref "U601") (pin "7") (pinfunction "ISET2_7") (pintype "input"))
    )
    (net (code "14") (name "Net-(U601-OUT)") (class "Default")
      (node (ref "R600") (pin "2") (pinfunction "2_2") (pintype "passive"))
      (node (ref "R604") (pin "2") (pinfunction "2_2") (pintype "passive"))
      (node (ref "U601") (pin "10") (pinfunction "OUT_10") (pintype "output"))
    )
    (net (code "15") (name "Net-(U601-PRETERM)") (class "Default")
      (node (ref "R606") (pin "1") (pinfunction "1_1") (pintype "passive"))
      (node (ref "U601") (pin "4") (pinfunction "PRETERM_4") (pintype "input"))
    )
    (net (code "16") (name "Net-(U601-~{PG})") (class "Default")
      (node (ref "TP600") (pin "1") (pinfunction "1_1") (pintype "passive"))
      (node (ref "U601") (pin "5") (pinfunction "~{PG}_5") (pintype "output"))
    )
    (net (code "17") (name "Net-(U605-OUT)") (class "Default")
      (node (ref "C636") (pin "2") (pinfunction "2_2") (pintype "passive"))
      (node (ref "R611") (pin "1") (pinfunction "1_1") (pintype "passive"))
      (node (ref "U605") (pin "2") (pinfunction "OUT_2") (pintype "power_in"))
      (node (ref "U605") (pin "4") (pinfunction "TAB_4") (pintype "power_in"))
    )
    (net (code "18") (name "Net-(U606-FB)") (class "Default")
      (node (ref "R613") (pin "1") (pinfunction "1_1") (pintype "passive"))
      (node (ref "R615") (pin "2") (pinfunction "2_2") (pintype "passive"))
      (node (ref "U606") (pin "4") (pinfunction "FB_4") (pintype "passive"))
    )
    (net (code "19") (name "Net-(U606-VOUT)") (class "Default")
      (node (ref "R612") (pin "2") (pinfunction "2_2") (pintype "passive"))
      (node (ref "R613") (pin "2") (pinfunction "2_2") (pintype "passive"))
      (node (ref "U606") (pin "2") (pinfunction "VOUT_2") (pintype "passive"))
    )
    (net (code "20") (name "VBAT") (class "Default")
      (node (ref "C600") (pin "2") (pinfunction "2_2") (pintype "passive"))
      (node (ref "C605") (pin "2") (pinfunction "2_2") (pintype "passive"))
      (node (ref "P600") (pin "3") (pinfunction "3_3") (pintype "passive"))
      (node (ref "R602") (pin "2") (pinfunction "2_2") (pintype "passive"))
      (node (ref "R604") (pin "1") (pinfunction "1_1") (pintype "passive"))
      (node (ref "U600") (pin "5") (pinfunction "VIN_5") (pintype "input"))
    )
    (net (code "21") (name "VBUS") (class "Default")
      (node (ref "C604") (pin "2") (pinfunction "2_2") (pintype "passive"))
      (node (ref "J600") (pin "1") (pinfunction "VBUS_1") (pintype "passive"))
      (node (ref "R603") (pin "2") (pinfunction "2_2") (pintype "passive"))
    )
    (net (code "22") (name "VCC1V3") (class "Default")
      (node (ref "C637") (pin "2") (pinfunction "2_2") (pintype "passive"))
      (node (ref "C638") (pin "2") (pinfunction "2_2") (pintype "passive"))
      (node (ref "C639") (pin "2") (pinfunction "2_2") (pintype "passive"))
      (node (ref "C640") (pin "2") (pinfunction "2_2") (pintype "passive"))
      (node (ref "C641") (pin "2") (pinfunction "2_2") (pintype "passive"))
      (node (ref "C642") (pin "2") (pinfunction "2_2") (pintype "passive"))
      (node (ref "C643") (pin "2") (pinfunction "2_2") (pintype "passive"))
      (node (ref "C644") (pin "2") (pinfunction "2_2") (pintype "passive"))
      (node (ref "C645") (pin "2") (pinfunction "2_2") (pintype "passive"))
      (node (ref "C646") (pin "2") (pinfunction "2_2") (pintype "passive"))
      (node (ref "C647") (pin "2") (pinfunction "2_2") (pintype "passive"))
      (node (ref "C648") (pin "2") (pinfunction "2_2") (pintype "passive"))
      (node (ref "C651") (pin "1") (pinfunction "1_1") (pintype "passive"))
      (node (ref "R612") (pin "1") (pinfunction "1_1") (pintype "passive"))
      (node (ref "U100") (pin "C9") (pinfunction "VDDINT_C9") (pintype "power_in"))
      (node (ref "U100") (pin "E10") (pinfunction "VDDINT_E10") (pintype "power_in"))
      (node (ref "U100") (pin "E7") (pinfunction "VDDINT_E7") (pintype "power_in"))
      (node (ref "U100") (pin "E8") (pinfunction "VDDINT_E8") (pintype "power_in"))
      (node (ref "U100") (pin "E9") (pinfunction "VDDINT_E9") (pintype "power_in"))
      (node (ref "U100") (pin "F10") (pinfunction "VDDINT_F10") (pintype "power_in"))
      (node (ref "U100") (pin "F3") (pinfunction "VDDINT_F3") (pintype "power_in"))
      (node (ref "U100") (pin "G10") (pinfunction "VDDINT_G10") (pintype "power_in"))
      (node (ref "U100") (pin "G3") (pinfunction "VDDINT_G3") (pintype "power_in"))
      (node (ref "U100") (pin "H10") (pinfunction "VDDINT_H10") (pintype "power_in"))
      (node (ref "U100") (pin "J10") (pinfunction "VDDINT_J10") (pintype "power_in"))
    )
    (net (code "23") (name "VCC1V8") (class "Default")
      (node (ref "R611") (pin "2") (pinfunction "2_2") (pintype "passive"))
    )
    (net (code "24") (name "VCC2V5") (class "Default")
      (node (ref "C612") (pin "2") (pinfunction "2_2") (pintype "passive"))
      (node (ref "U100") (pin "B1") (pinfunction "VDDOTP_B1") (pintype "power_in"))
      (node (ref "U100") (pin "D3") (pinfunction "VPPOTP_D3") (pintype "power_in"))
      (node (ref "U604") (pin "2") (pinfunction "OUT_2") (pintype "passive"))
    )
    (net (code "25") (name "VCC3V3") (class "Default")
      (node (ref "C610") (pin "1") (pinfunction "1_1") (pintype "passive"))
      (node (ref "C611") (pin "2") (pinfunction "2_2") (pintype "passive"))
      (node (ref "C613") (pin "2") (pinfunction "2_2") (pintype "passive"))
      (node (ref "C614") (pin "2") (pinfunction "2_2") (pintype "passive"))
      (node (ref "C615") (pin "2") (pinfunction "2_2") (pintype "passive"))
      (node (ref "C616") (pin "2") (pinfunction "2_2") (pintype "passive"))
      (node (ref "C617") (pin "2") (pinfunction "2_2") (pintype "passive"))
      (node (ref "C618") (pin "2") (pinfunction "2_2") (pintype "passive"))
      (node (ref "C619") (pin "2") (pinfunction "2_2") (pintype "passive"))
      (node (ref "C620") (pin "2") (pinfunction "2_2") (pintype "passive"))
      (node (ref "C621") (pin "2") (pinfunction "2_2") (pintype "passive"))
      (node (ref "C622") (pin "2") (pinfunction "2_2") (pintype "passive"))
      (node (ref "C623") (pin "2") (pinfunction "2_2") (pintype "passive"))
      (node (ref "C624") (pin "2") (pinfunction "2_2") (pintype "passive"))
      (node (ref "C625") (pin "2") (pinfunction "2_2") (pintype "passive"))
      (node (ref "C626") (pin "2") (pinfunction "2_2") (pintype "passive"))
      (node (ref "C627") (pin "2") (pinfunction "2_2") (pintype "passive"))
      (node (ref "C628") (pin "2") (pinfunction "2_2") (pintype "passive"))
      (node (ref "C629") (pin "2") (pinfunction "2_2") (pintype "passive"))
      (node (ref "C630") (pin "2") (pinfunction "2_2") (pintype "passive"))
      (node (ref "C631") (pin "2") (pinfunction "2_2") (pintype "passive"))
      (node (ref "C632") (pin "2") (pinfunction "2_2") (pintype "passive"))
      (node (ref "C633") (pin "2") (pinfunction "2_2") (pintype "passive"))
      (node (ref "C634") (pin "2") (pinfunction "2_2") (pintype "passive"))
      (node (ref "C635") (pin "2") (pinfunction "2_2") (pintype "passive"))
      (node (ref "C649") (pin "1") (pinfunction "1_1") (pintype "passive"))
      (node (ref "C650") (pin "2") (pinfunction "2_2") (pintype "passive"))
      (node (ref "C652") (pin "2") (pinfunction "2_2") (pintype "passive"))
      (node (ref "C653") (pin "2") (pinfunction "2_2") (pintype "passive"))
      (node (ref "C654") (pin "2") (pinfunction "2_2") (pintype "passive"))
      (node (ref "C655") (pin "2") (pinfunction "2_2") (pintype "passive"))
      (node (ref "C656") (pin "2") (pinfunction "2_2") (pintype "passive"))
      (node (ref "R601") (pin "2") (pinfunction "2_2") (pintype "passive"))
      (node (ref "R607") (pin "1") (pinfunction "1_1") (pintype "passive"))
      (node (ref "R614") (pin "1") (pinfunction "1_1") (pintype "passive"))
      (node (ref "U100") (pin "B12") (pinfunction "VDDRTC_B12") (pintype "power_in"))
      (node (ref "U100") (pin "B13") (pinfunction "VDDEXT_B13") (pintype "power_in"))
      (node (ref "U100") (pin "B9") (pinfunction "VDDEXT_B9") (pintype "power_in"))
      (node (ref "U100") (pin "C10") (pinfunction "VDDEXT_C10") (pintype "power_in"))
      (node (ref "U100") (pin "C5") (pinfunction "VDDEXT_C5") (pintype "power_in"))
      (node (ref "U100") (pin "C6") (pinfunction "VDDEXT_C6") (pintype "power_in"))
      (node (ref "U100") (pin "C8") (pinfunction "VDDEXT_C8") (pintype "power_in"))
      (node (ref "U100") (pin "D12") (pinfunction "VDDFLASH_D12") (pintype "power_in"))
      (node (ref "U100") (pin "E1") (pinfunction "VDDFLASH_E1") (pintype "power_in"))
      (node (ref "U100") (pin "E12") (pinfunction "VDDMEM_E12") (pintype "power_in"))
      (node (ref "U100") (pin "E5") (pinfunction "VDDEXT_E5") (pintype "power_in"))
      (node (ref "U100") (pin "E6") (pinfunction "VDDEXT_E6") (pintype "power_in"))
      (node (ref "U100") (pin "F5") (pinfunction "VDDEXT_F5") (pintype "power_in"))
      (node (ref "U100") (pin "G5") (pinfunction "VDDEXT_G5") (pintype "power_in"))
      (node (ref "U100") (pin "H5") (pinfunction "VDDEXT_H5") (pintype "power_in"))
      (node (ref "U100") (pin "J2") (pinfunction "VDDFLASH_J2") (pintype "power_in"))
      (node (ref "U100") (pin "J5") (pinfunction "VDDMEM_J5") (pintype "power_in"))
      (node (ref "U100") (pin "K10") (pinfunction "VDDMEM_K10") (pintype "power_in"))
      (node (ref "U100") (pin "K5") (pinfunction "VDDMEM_K5") (pintype "power_in"))
      (node (ref "U100") (pin "K6") (pinfunction "VDDMEM_K6") (pintype "power_in"))
      (node (ref "U100") (pin "K7") (pinfunction "VDDMEM_K7") (pintype "power_in"))
      (node (ref "U100") (pin "K8") (pinfunction "VDDMEM_K8") (pintype "power_in"))
      (node (ref "U100") (pin "K9") (pinfunction "VDDMEM_K9") (pintype "power_in"))
      (node (ref "U604") (pin "3") (pinfunction "IN_3") (pintype "passive"))
      (node (ref "U605") (pin "3") (pinfunction "IN_3") (pintype "power_in"))
      (node (ref "U606") (pin "1") (pinfunction "VIN_1") (pintype "passive"))
    )
    (net (code "26") (name "unconnected-(J600-D+-Pad3)") (class "Default")
      (node (ref "J600") (pin "3") (pinfunction "D+_3") (pintype "passive+no_connect"))
    )
    (net (code "27") (name "unconnected-(J600-D--Pad2)") (class "Default")
      (node (ref "J600") (pin "2") (pinfunction "D-_2") (pintype "passive+no_connect"))
    )
    (net (code "28") (name "unconnected-(U601-NC-Pad6)") (class "Default")
      (node (ref "U601") (pin "6") (pinfunction "NC_6") (pintype "passive+no_connect"))
    )
  )
)
